# TopSide.net
KiCad netlist of a schematic drawn in Altium Designer
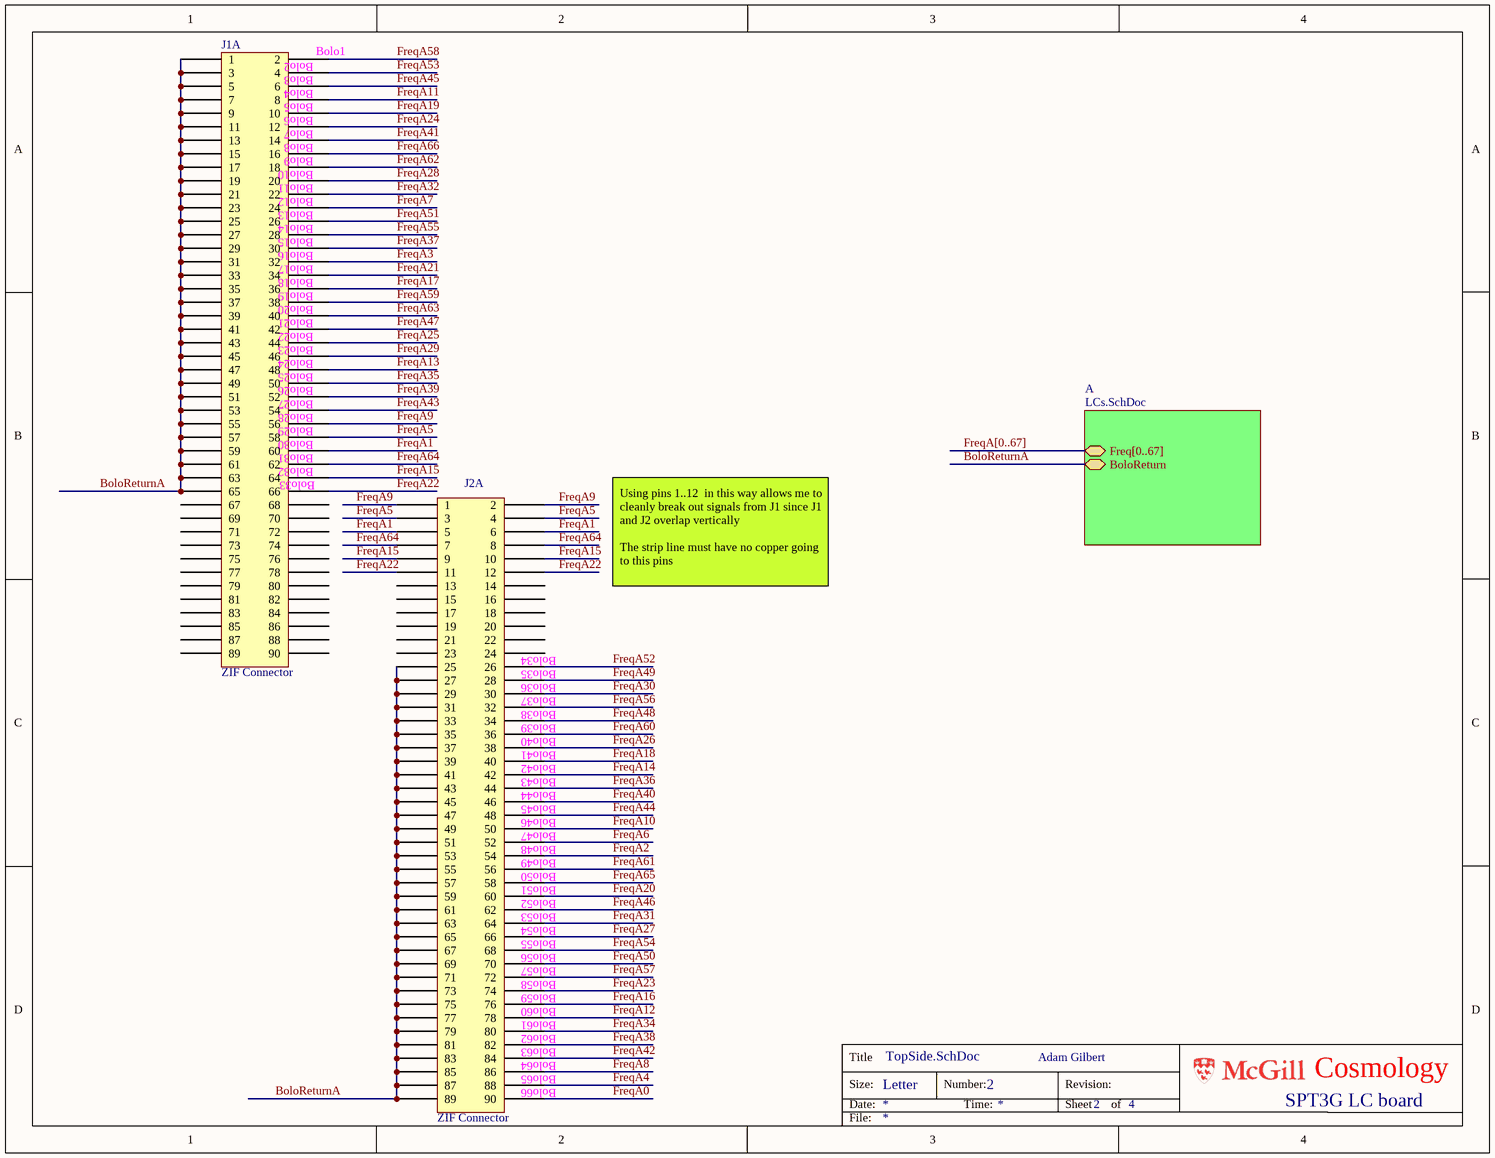
[diagram p0: TopSide.SchDoc]

(export (version "E")
  (design (tool "Eeschema 10.0.6"))
  (components
    (comp (ref "J1A")
      (value "ZIF Connector")
      (footprint "LCBoard_ZIFCon")
      (libsource (lib "SPT3G_LCBoard") (part "LCboard_FH16-90S-0.3SHW(05)"))
    )
    (comp (ref "J2A")
      (value "ZIF Connector")
      (footprint "LCBoard_ZIFCon")
      (libsource (lib "SPT3G_LCBoard") (part "LCboard_FH16-90S-0.3SHW(05)"))
    )
  )
  (nets
    (net (code "3") (name "/BoloReturnA") (class "Default")
      (node (ref "J1A") (pin "1") (pinfunction "1_1") (pintype "passive"))
      (node (ref "J1A") (pin "11") (pinfunction "11_11") (pintype "passive"))
      (node (ref "J1A") (pin "13") (pinfunction "13_13") (pintype "passive"))
      (node (ref "J1A") (pin "15") (pinfunction "15_15") (pintype "passive"))
      (node (ref "J1A") (pin "17") (pinfunction "17_17") (pintype "passive"))
      (node (ref "J1A") (pin "19") (pinfunction "19_19") (pintype "passive"))
      (node (ref "J1A") (pin "21") (pinfunction "21_21") (pintype "passive"))
      (node (ref "J1A") (pin "23") (pinfunction "23_23") (pintype "passive"))
      (node (ref "J1A") (pin "25") (pinfunction "25_25") (pintype "passive"))
      (node (ref "J1A") (pin "27") (pinfunction "27_27") (pintype "passive"))
      (node (ref "J1A") (pin "29") (pinfunction "29_29") (pintype "passive"))
      (node (ref "J1A") (pin "3") (pinfunction "3_3") (pintype "passive"))
      (node (ref "J1A") (pin "31") (pinfunction "31_31") (pintype "passive"))
      (node (ref "J1A") (pin "33") (pinfunction "33_33") (pintype "passive"))
      (node (ref "J1A") (pin "35") (pinfunction "35_35") (pintype "passive"))
      (node (ref "J1A") (pin "37") (pinfunction "37_37") (pintype "passive"))
      (node (ref "J1A") (pin "39") (pinfunction "39_39") (pintype "passive"))
      (node (ref "J1A") (pin "41") (pinfunction "41_41") (pintype "passive"))
      (node (ref "J1A") (pin "43") (pinfunction "43_43") (pintype "passive"))
      (node (ref "J1A") (pin "45") (pinfunction "45_45") (pintype "passive"))
      (node (ref "J1A") (pin "47") (pinfunction "47_47") (pintype "passive"))
      (node (ref "J1A") (pin "49") (pinfunction "49_49") (pintype "passive"))
      (node (ref "J1A") (pin "5") (pinfunction "5_5") (pintype "passive"))
      (node (ref "J1A") (pin "51") (pinfunction "51_51") (pintype "passive"))
      (node (ref "J1A") (pin "53") (pinfunction "53_53") (pintype "passive"))
      (node (ref "J1A") (pin "55") (pinfunction "55_55") (pintype "passive"))
      (node (ref "J1A") (pin "57") (pinfunction "57_57") (pintype "passive"))
      (node (ref "J1A") (pin "59") (pinfunction "59_59") (pintype "passive"))
      (node (ref "J1A") (pin "61") (pinfunction "61_61") (pintype "passive"))
      (node (ref "J1A") (pin "63") (pinfunction "63_63") (pintype "passive"))
      (node (ref "J1A") (pin "65") (pinfunction "65_65") (pintype "passive"))
      (node (ref "J1A") (pin "7") (pinfunction "7_7") (pintype "passive"))
      (node (ref "J1A") (pin "9") (pinfunction "9_9") (pintype "passive"))
      (node (ref "J2A") (pin "25") (pinfunction "25_25") (pintype "passive"))
      (node (ref "J2A") (pin "27") (pinfunction "27_27") (pintype "passive"))
      (node (ref "J2A") (pin "29") (pinfunction "29_29") (pintype "passive"))
      (node (ref "J2A") (pin "31") (pinfunction "31_31") (pintype "passive"))
      (node (ref "J2A") (pin "33") (pinfunction "33_33") (pintype "passive"))
      (node (ref "J2A") (pin "35") (pinfunction "35_35") (pintype "passive"))
      (node (ref "J2A") (pin "37") (pinfunction "37_37") (pintype "passive"))
      (node (ref "J2A") (pin "39") (pinfunction "39_39") (pintype "passive"))
      (node (ref "J2A") (pin "41") (pinfunction "41_41") (pintype "passive"))
      (node (ref "J2A") (pin "43") (pinfunction "43_43") (pintype "passive"))
      (node (ref "J2A") (pin "45") (pinfunction "45_45") (pintype "passive"))
      (node (ref "J2A") (pin "47") (pinfunction "47_47") (pintype "passive"))
      (node (ref "J2A") (pin "49") (pinfunction "49_49") (pintype "passive"))
      (node (ref "J2A") (pin "51") (pinfunction "51_51") (pintype "passive"))
      (node (ref "J2A") (pin "53") (pinfunction "53_53") (pintype "passive"))
      (node (ref "J2A") (pin "55") (pinfunction "55_55") (pintype "passive"))
      (node (ref "J2A") (pin "57") (pinfunction "57_57") (pintype "passive"))
      (node (ref "J2A") (pin "59") (pinfunction "59_59") (pintype "passive"))
      (node (ref "J2A") (pin "61") (pinfunction "61_61") (pintype "passive"))
      (node (ref "J2A") (pin "63") (pinfunction "63_63") (pintype "passive"))
      (node (ref "J2A") (pin "65") (pinfunction "65_65") (pintype "passive"))
      (node (ref "J2A") (pin "67") (pinfunction "67_67") (pintype "passive"))
      (node (ref "J2A") (pin "69") (pinfunction "69_69") (pintype "passive"))
      (node (ref "J2A") (pin "71") (pinfunction "71_71") (pintype "passive"))
      (node (ref "J2A") (pin "73") (pinfunction "73_73") (pintype "passive"))
      (node (ref "J2A") (pin "75") (pinfunction "75_75") (pintype "passive"))
      (node (ref "J2A") (pin "77") (pinfunction "77_77") (pintype "passive"))
      (node (ref "J2A") (pin "79") (pinfunction "79_79") (pintype "passive"))
      (node (ref "J2A") (pin "81") (pinfunction "81_81") (pintype "passive"))
      (node (ref "J2A") (pin "83") (pinfunction "83_83") (pintype "passive"))
      (node (ref "J2A") (pin "85") (pinfunction "85_85") (pintype "passive"))
      (node (ref "J2A") (pin "87") (pinfunction "87_87") (pintype "passive"))
      (node (ref "J2A") (pin "89") (pinfunction "89_89") (pintype "passive"))
    )
    (net (code "4") (name "/FreqA0") (class "Default")
      (node (ref "J2A") (pin "90") (pinfunction "90_90") (pintype "passive"))
    )
    (net (code "5") (name "/FreqA1") (class "Default")
      (node (ref "J1A") (pin "60") (pinfunction "60_60") (pintype "passive"))
      (node (ref "J2A") (pin "5") (pinfunction "5_5") (pintype "passive"))
      (node (ref "J2A") (pin "6") (pinfunction "6_6") (pintype "passive"))
    )
    (net (code "6") (name "/FreqA2") (class "Default")
      (node (ref "J2A") (pin "54") (pinfunction "54_54") (pintype "passive"))
    )
    (net (code "7") (name "/FreqA3") (class "Default")
      (node (ref "J1A") (pin "32") (pinfunction "32_32") (pintype "passive"))
    )
    (net (code "8") (name "/FreqA4") (class "Default")
      (node (ref "J2A") (pin "88") (pinfunction "88_88") (pintype "passive"))
    )
    (net (code "9") (name "/FreqA5") (class "Default")
      (node (ref "J1A") (pin "58") (pinfunction "58_58") (pintype "passive"))
      (node (ref "J2A") (pin "3") (pinfunction "3_3") (pintype "passive"))
      (node (ref "J2A") (pin "4") (pinfunction "4_4") (pintype "passive"))
    )
    (net (code "10") (name "/FreqA6") (class "Default")
      (node (ref "J2A") (pin "52") (pinfunction "52_52") (pintype "passive"))
    )
    (net (code "11") (name "/FreqA7") (class "Default")
      (node (ref "J1A") (pin "24") (pinfunction "24_24") (pintype "passive"))
    )
    (net (code "12") (name "/FreqA8") (class "Default")
      (node (ref "J2A") (pin "86") (pinfunction "86_86") (pintype "passive"))
    )
    (net (code "13") (name "/FreqA9") (class "Default")
      (node (ref "J1A") (pin "56") (pinfunction "56_56") (pintype "passive"))
      (node (ref "J2A") (pin "1") (pinfunction "1_1") (pintype "passive"))
      (node (ref "J2A") (pin "2") (pinfunction "2_2") (pintype "passive"))
    )
    (net (code "14") (name "/FreqA10") (class "Default")
      (node (ref "J2A") (pin "50") (pinfunction "50_50") (pintype "passive"))
    )
    (net (code "15") (name "/FreqA11") (class "Default")
      (node (ref "J1A") (pin "8") (pinfunction "8_8") (pintype "passive"))
    )
    (net (code "16") (name "/FreqA12") (class "Default")
      (node (ref "J2A") (pin "78") (pinfunction "78_78") (pintype "passive"))
    )
    (net (code "17") (name "/FreqA13") (class "Default")
      (node (ref "J1A") (pin "48") (pinfunction "48_48") (pintype "passive"))
    )
    (net (code "18") (name "/FreqA14") (class "Default")
      (node (ref "J2A") (pin "42") (pinfunction "42_42") (pintype "passive"))
    )
    (net (code "19") (name "/FreqA15") (class "Default")
      (node (ref "J1A") (pin "64") (pinfunction "64_64") (pintype "passive"))
      (node (ref "J2A") (pin "10") (pinfunction "10_10") (pintype "passive"))
      (node (ref "J2A") (pin "9") (pinfunction "9_9") (pintype "passive"))
    )
    (net (code "20") (name "/FreqA16") (class "Default")
      (node (ref "J2A") (pin "76") (pinfunction "76_76") (pintype "passive"))
    )
    (net (code "21") (name "/FreqA17") (class "Default")
      (node (ref "J1A") (pin "36") (pinfunction "36_36") (pintype "passive"))
    )
    (net (code "22") (name "/FreqA18") (class "Default")
      (node (ref "J2A") (pin "40") (pinfunction "40_40") (pintype "passive"))
    )
    (net (code "23") (name "/FreqA19") (class "Default")
      (node (ref "J1A") (pin "10") (pinfunction "10_10") (pintype "passive"))
    )
    (net (code "24") (name "/FreqA20") (class "Default")
      (node (ref "J2A") (pin "60") (pinfunction "60_60") (pintype "passive"))
    )
    (net (code "25") (name "/FreqA21") (class "Default")
      (node (ref "J1A") (pin "34") (pinfunction "34_34") (pintype "passive"))
    )
    (net (code "26") (name "/FreqA22") (class "Default")
      (node (ref "J1A") (pin "66") (pinfunction "66_66") (pintype "passive"))
      (node (ref "J2A") (pin "11") (pinfunction "11_11") (pintype "passive"))
      (node (ref "J2A") (pin "12") (pinfunction "12_12") (pintype "passive"))
    )
    (net (code "27") (name "/FreqA23") (class "Default")
      (node (ref "J2A") (pin "74") (pinfunction "74_74") (pintype "passive"))
    )
    (net (code "28") (name "/FreqA24") (class "Default")
      (node (ref "J1A") (pin "12") (pinfunction "12_12") (pintype "passive"))
    )
    (net (code "29") (name "/FreqA25") (class "Default")
      (node (ref "J1A") (pin "44") (pinfunction "44_44") (pintype "passive"))
    )
    (net (code "30") (name "/FreqA26") (class "Default")
      (node (ref "J2A") (pin "38") (pinfunction "38_38") (pintype "passive"))
    )
    (net (code "31") (name "/FreqA27") (class "Default")
      (node (ref "J2A") (pin "66") (pinfunction "66_66") (pintype "passive"))
    )
    (net (code "32") (name "/FreqA28") (class "Default")
      (node (ref "J1A") (pin "20") (pinfunction "20_20") (pintype "passive"))
    )
    (net (code "33") (name "/FreqA29") (class "Default")
      (node (ref "J1A") (pin "46") (pinfunction "46_46") (pintype "passive"))
    )
    (net (code "34") (name "/FreqA30") (class "Default")
      (node (ref "J2A") (pin "30") (pinfunction "30_30") (pintype "passive"))
    )
    (net (code "35") (name "/FreqA31") (class "Default")
      (node (ref "J2A") (pin "64") (pinfunction "64_64") (pintype "passive"))
    )
    (net (code "36") (name "/FreqA32") (class "Default")
      (node (ref "J1A") (pin "22") (pinfunction "22_22") (pintype "passive"))
    )
    (net (code "37") (name "/FreqA34") (class "Default")
      (node (ref "J2A") (pin "80") (pinfunction "80_80") (pintype "passive"))
    )
    (net (code "38") (name "/FreqA35") (class "Default")
      (node (ref "J1A") (pin "50") (pinfunction "50_50") (pintype "passive"))
    )
    (net (code "39") (name "/FreqA36") (class "Default")
      (node (ref "J2A") (pin "44") (pinfunction "44_44") (pintype "passive"))
    )
    (net (code "40") (name "/FreqA37") (class "Default")
      (node (ref "J1A") (pin "30") (pinfunction "30_30") (pintype "passive"))
    )
    (net (code "41") (name "/FreqA38") (class "Default")
      (node (ref "J2A") (pin "82") (pinfunction "82_82") (pintype "passive"))
    )
    (net (code "42") (name "/FreqA39") (class "Default")
      (node (ref "J1A") (pin "52") (pinfunction "52_52") (pintype "passive"))
    )
    (net (code "43") (name "/FreqA40") (class "Default")
      (node (ref "J2A") (pin "46") (pinfunction "46_46") (pintype "passive"))
    )
    (net (code "44") (name "/FreqA41") (class "Default")
      (node (ref "J1A") (pin "14") (pinfunction "14_14") (pintype "passive"))
    )
    (net (code "45") (name "/FreqA42") (class "Default")
      (node (ref "J2A") (pin "84") (pinfunction "84_84") (pintype "passive"))
    )
    (net (code "46") (name "/FreqA43") (class "Default")
      (node (ref "J1A") (pin "54") (pinfunction "54_54") (pintype "passive"))
    )
    (net (code "47") (name "/FreqA44") (class "Default")
      (node (ref "J2A") (pin "48") (pinfunction "48_48") (pintype "passive"))
    )
    (net (code "48") (name "/FreqA45") (class "Default")
      (node (ref "J1A") (pin "6") (pinfunction "6_6") (pintype "passive"))
    )
    (net (code "49") (name "/FreqA46") (class "Default")
      (node (ref "J2A") (pin "62") (pinfunction "62_62") (pintype "passive"))
    )
    (net (code "50") (name "/FreqA47") (class "Default")
      (node (ref "J1A") (pin "42") (pinfunction "42_42") (pintype "passive"))
    )
    (net (code "51") (name "/FreqA48") (class "Default")
      (node (ref "J2A") (pin "34") (pinfunction "34_34") (pintype "passive"))
    )
    (net (code "52") (name "/FreqA49") (class "Default")
      (node (ref "J2A") (pin "28") (pinfunction "28_28") (pintype "passive"))
    )
    (net (code "53") (name "/FreqA50") (class "Default")
      (node (ref "J2A") (pin "70") (pinfunction "70_70") (pintype "passive"))
    )
    (net (code "54") (name "/FreqA51") (class "Default")
      (node (ref "J1A") (pin "26") (pinfunction "26_26") (pintype "passive"))
    )
    (net (code "55") (name "/FreqA52") (class "Default")
      (node (ref "J2A") (pin "26") (pinfunction "26_26") (pintype "passive"))
    )
    (net (code "56") (name "/FreqA53") (class "Default")
      (node (ref "J1A") (pin "4") (pinfunction "4_4") (pintype "passive"))
    )
    (net (code "57") (name "/FreqA54") (class "Default")
      (node (ref "J2A") (pin "68") (pinfunction "68_68") (pintype "passive"))
    )
    (net (code "58") (name "/FreqA55") (class "Default")
      (node (ref "J1A") (pin "28") (pinfunction "28_28") (pintype "passive"))
    )
    (net (code "59") (name "/FreqA56") (class "Default")
      (node (ref "J2A") (pin "32") (pinfunction "32_32") (pintype "passive"))
    )
    (net (code "60") (name "/FreqA57") (class "Default")
      (node (ref "J2A") (pin "72") (pinfunction "72_72") (pintype "passive"))
    )
    (net (code "61") (name "/FreqA58") (class "Default")
      (node (ref "J1A") (pin "2") (pinfunction "2_2") (pintype "passive"))
    )
    (net (code "62") (name "/FreqA59") (class "Default")
      (node (ref "J1A") (pin "38") (pinfunction "38_38") (pintype "passive"))
    )
    (net (code "63") (name "/FreqA60") (class "Default")
      (node (ref "J2A") (pin "36") (pinfunction "36_36") (pintype "passive"))
    )
    (net (code "64") (name "/FreqA61") (class "Default")
      (node (ref "J2A") (pin "56") (pinfunction "56_56") (pintype "passive"))
    )
    (net (code "65") (name "/FreqA62") (class "Default")
      (node (ref "J1A") (pin "18") (pinfunction "18_18") (pintype "passive"))
    )
    (net (code "66") (name "/FreqA63") (class "Default")
      (node (ref "J1A") (pin "40") (pinfunction "40_40") (pintype "passive"))
    )
    (net (code "67") (name "/FreqA64") (class "Default")
      (node (ref "J1A") (pin "62") (pinfunction "62_62") (pintype "passive"))
      (node (ref "J2A") (pin "7") (pinfunction "7_7") (pintype "passive"))
      (node (ref "J2A") (pin "8") (pinfunction "8_8") (pintype "passive"))
    )
    (net (code "68") (name "/FreqA65") (class "Default")
      (node (ref "J2A") (pin "58") (pinfunction "58_58") (pintype "passive"))
    )
    (net (code "69") (name "/FreqA66") (class "Default")
      (node (ref "J1A") (pin "16") (pinfunction "16_16") (pintype "passive"))
    )
    (net (code "71") (name "unconnected-(J1A-Pad67)") (class "Default")
      (node (ref "J1A") (pin "67") (pinfunction "67_67") (pintype "passive"))
    )
    (net (code "72") (name "unconnected-(J1A-Pad68)") (class "Default")
      (node (ref "J1A") (pin "68") (pinfunction "68_68") (pintype "passive"))
    )
    (net (code "73") (name "unconnected-(J1A-Pad69)") (class "Default")
      (node (ref "J1A") (pin "69") (pinfunction "69_69") (pintype "passive"))
    )
    (net (code "74") (name "unconnected-(J1A-Pad70)") (class "Default")
      (node (ref "J1A") (pin "70") (pinfunction "70_70") (pintype "passive"))
    )
    (net (code "75") (name "unconnected-(J1A-Pad71)") (class "Default")
      (node (ref "J1A") (pin "71") (pinfunction "71_71") (pintype "passive"))
    )
    (net (code "76") (name "unconnected-(J1A-Pad72)") (class "Default")
      (node (ref "J1A") (pin "72") (pinfunction "72_72") (pintype "passive"))
    )
    (net (code "77") (name "unconnected-(J1A-Pad73)") (class "Default")
      (node (ref "J1A") (pin "73") (pinfunction "73_73") (pintype "passive"))
    )
    (net (code "78") (name "unconnected-(J1A-Pad74)") (class "Default")
      (node (ref "J1A") (pin "74") (pinfunction "74_74") (pintype "passive"))
    )
    (net (code "79") (name "unconnected-(J1A-Pad75)") (class "Default")
      (node (ref "J1A") (pin "75") (pinfunction "75_75") (pintype "passive"))
    )
    (net (code "80") (name "unconnected-(J1A-Pad76)") (class "Default")
      (node (ref "J1A") (pin "76") (pinfunction "76_76") (pintype "passive"))
    )
    (net (code "81") (name "unconnected-(J1A-Pad77)") (class "Default")
      (node (ref "J1A") (pin "77") (pinfunction "77_77") (pintype "passive"))
    )
    (net (code "82") (name "unconnected-(J1A-Pad78)") (class "Default")
      (node (ref "J1A") (pin "78") (pinfunction "78_78") (pintype "passive"))
    )
    (net (code "83") (name "unconnected-(J1A-Pad79)") (class "Default")
      (node (ref "J1A") (pin "79") (pinfunction "79_79") (pintype "passive"))
    )
    (net (code "84") (name "unconnected-(J1A-Pad80)") (class "Default")
      (node (ref "J1A") (pin "80") (pinfunction "80_80") (pintype "passive"))
    )
    (net (code "85") (name "unconnected-(J1A-Pad81)") (class "Default")
      (node (ref "J1A") (pin "81") (pinfunction "81_81") (pintype "passive"))
    )
    (net (code "86") (name "unconnected-(J1A-Pad82)") (class "Default")
      (node (ref "J1A") (pin "82") (pinfunction "82_82") (pintype "passive"))
    )
    (net (code "87") (name "unconnected-(J1A-Pad83)") (class "Default")
      (node (ref "J1A") (pin "83") (pinfunction "83_83") (pintype "passive"))
    )
    (net (code "88") (name "unconnected-(J1A-Pad84)") (class "Default")
      (node (ref "J1A") (pin "84") (pinfunction "84_84") (pintype "passive"))
    )
    (net (code "89") (name "unconnected-(J1A-Pad85)") (class "Default")
      (node (ref "J1A") (pin "85") (pinfunction "85_85") (pintype "passive"))
    )
    (net (code "90") (name "unconnected-(J1A-Pad86)") (class "Default")
      (node (ref "J1A") (pin "86") (pinfunction "86_86") (pintype "passive"))
    )
    (net (code "91") (name "unconnected-(J1A-Pad87)") (class "Default")
      (node (ref "J1A") (pin "87") (pinfunction "87_87") (pintype "passive"))
    )
    (net (code "92") (name "unconnected-(J1A-Pad88)") (class "Default")
      (node (ref "J1A") (pin "88") (pinfunction "88_88") (pintype "passive"))
    )
    (net (code "93") (name "unconnected-(J1A-Pad89)") (class "Default")
      (node (ref "J1A") (pin "89") (pinfunction "89_89") (pintype "passive"))
    )
    (net (code "94") (name "unconnected-(J1A-Pad90)") (class "Default")
      (node (ref "J1A") (pin "90") (pinfunction "90_90") (pintype "passive"))
    )
    (net (code "95") (name "unconnected-(J2A-Pad13)") (class "Default")
      (node (ref "J2A") (pin "13") (pinfunction "13_13") (pintype "passive"))
    )
    (net (code "96") (name "unconnected-(J2A-Pad14)") (class "Default")
      (node (ref "J2A") (pin "14") (pinfunction "14_14") (pintype "passive"))
    )
    (net (code "97") (name "unconnected-(J2A-Pad15)") (class "Default")
      (node (ref "J2A") (pin "15") (pinfunction "15_15") (pintype "passive"))
    )
    (net (code "98") (name "unconnected-(J2A-Pad16)") (class "Default")
      (node (ref "J2A") (pin "16") (pinfunction "16_16") (pintype "passive"))
    )
    (net (code "99") (name "unconnected-(J2A-Pad17)") (class "Default")
      (node (ref "J2A") (pin "17") (pinfunction "17_17") (pintype "passive"))
    )
    (net (code "100") (name "unconnected-(J2A-Pad18)") (class "Default")
      (node (ref "J2A") (pin "18") (pinfunction "18_18") (pintype "passive"))
    )
    (net (code "101") (name "unconnected-(J2A-Pad19)") (class "Default")
      (node (ref "J2A") (pin "19") (pinfunction "19_19") (pintype "passive"))
    )
    (net (code "102") (name "unconnected-(J2A-Pad20)") (class "Default")
      (node (ref "J2A") (pin "20") (pinfunction "20_20") (pintype "passive"))
    )
    (net (code "103") (name "unconnected-(J2A-Pad21)") (class "Default")
      (node (ref "J2A") (pin "21") (pinfunction "21_21") (pintype "passive"))
    )
    (net (code "104") (name "unconnected-(J2A-Pad22)") (class "Default")
      (node (ref "J2A") (pin "22") (pinfunction "22_22") (pintype "passive"))
    )
    (net (code "105") (name "unconnected-(J2A-Pad23)") (class "Default")
      (node (ref "J2A") (pin "23") (pinfunction "23_23") (pintype "passive"))
    )
    (net (code "106") (name "unconnected-(J2A-Pad24)") (class "Default")
      (node (ref "J2A") (pin "24") (pinfunction "24_24") (pintype "passive"))
    )
  )
)
